# EE209_Schematic.net
KiCad netlist of a schematic drawn in Altium Designer
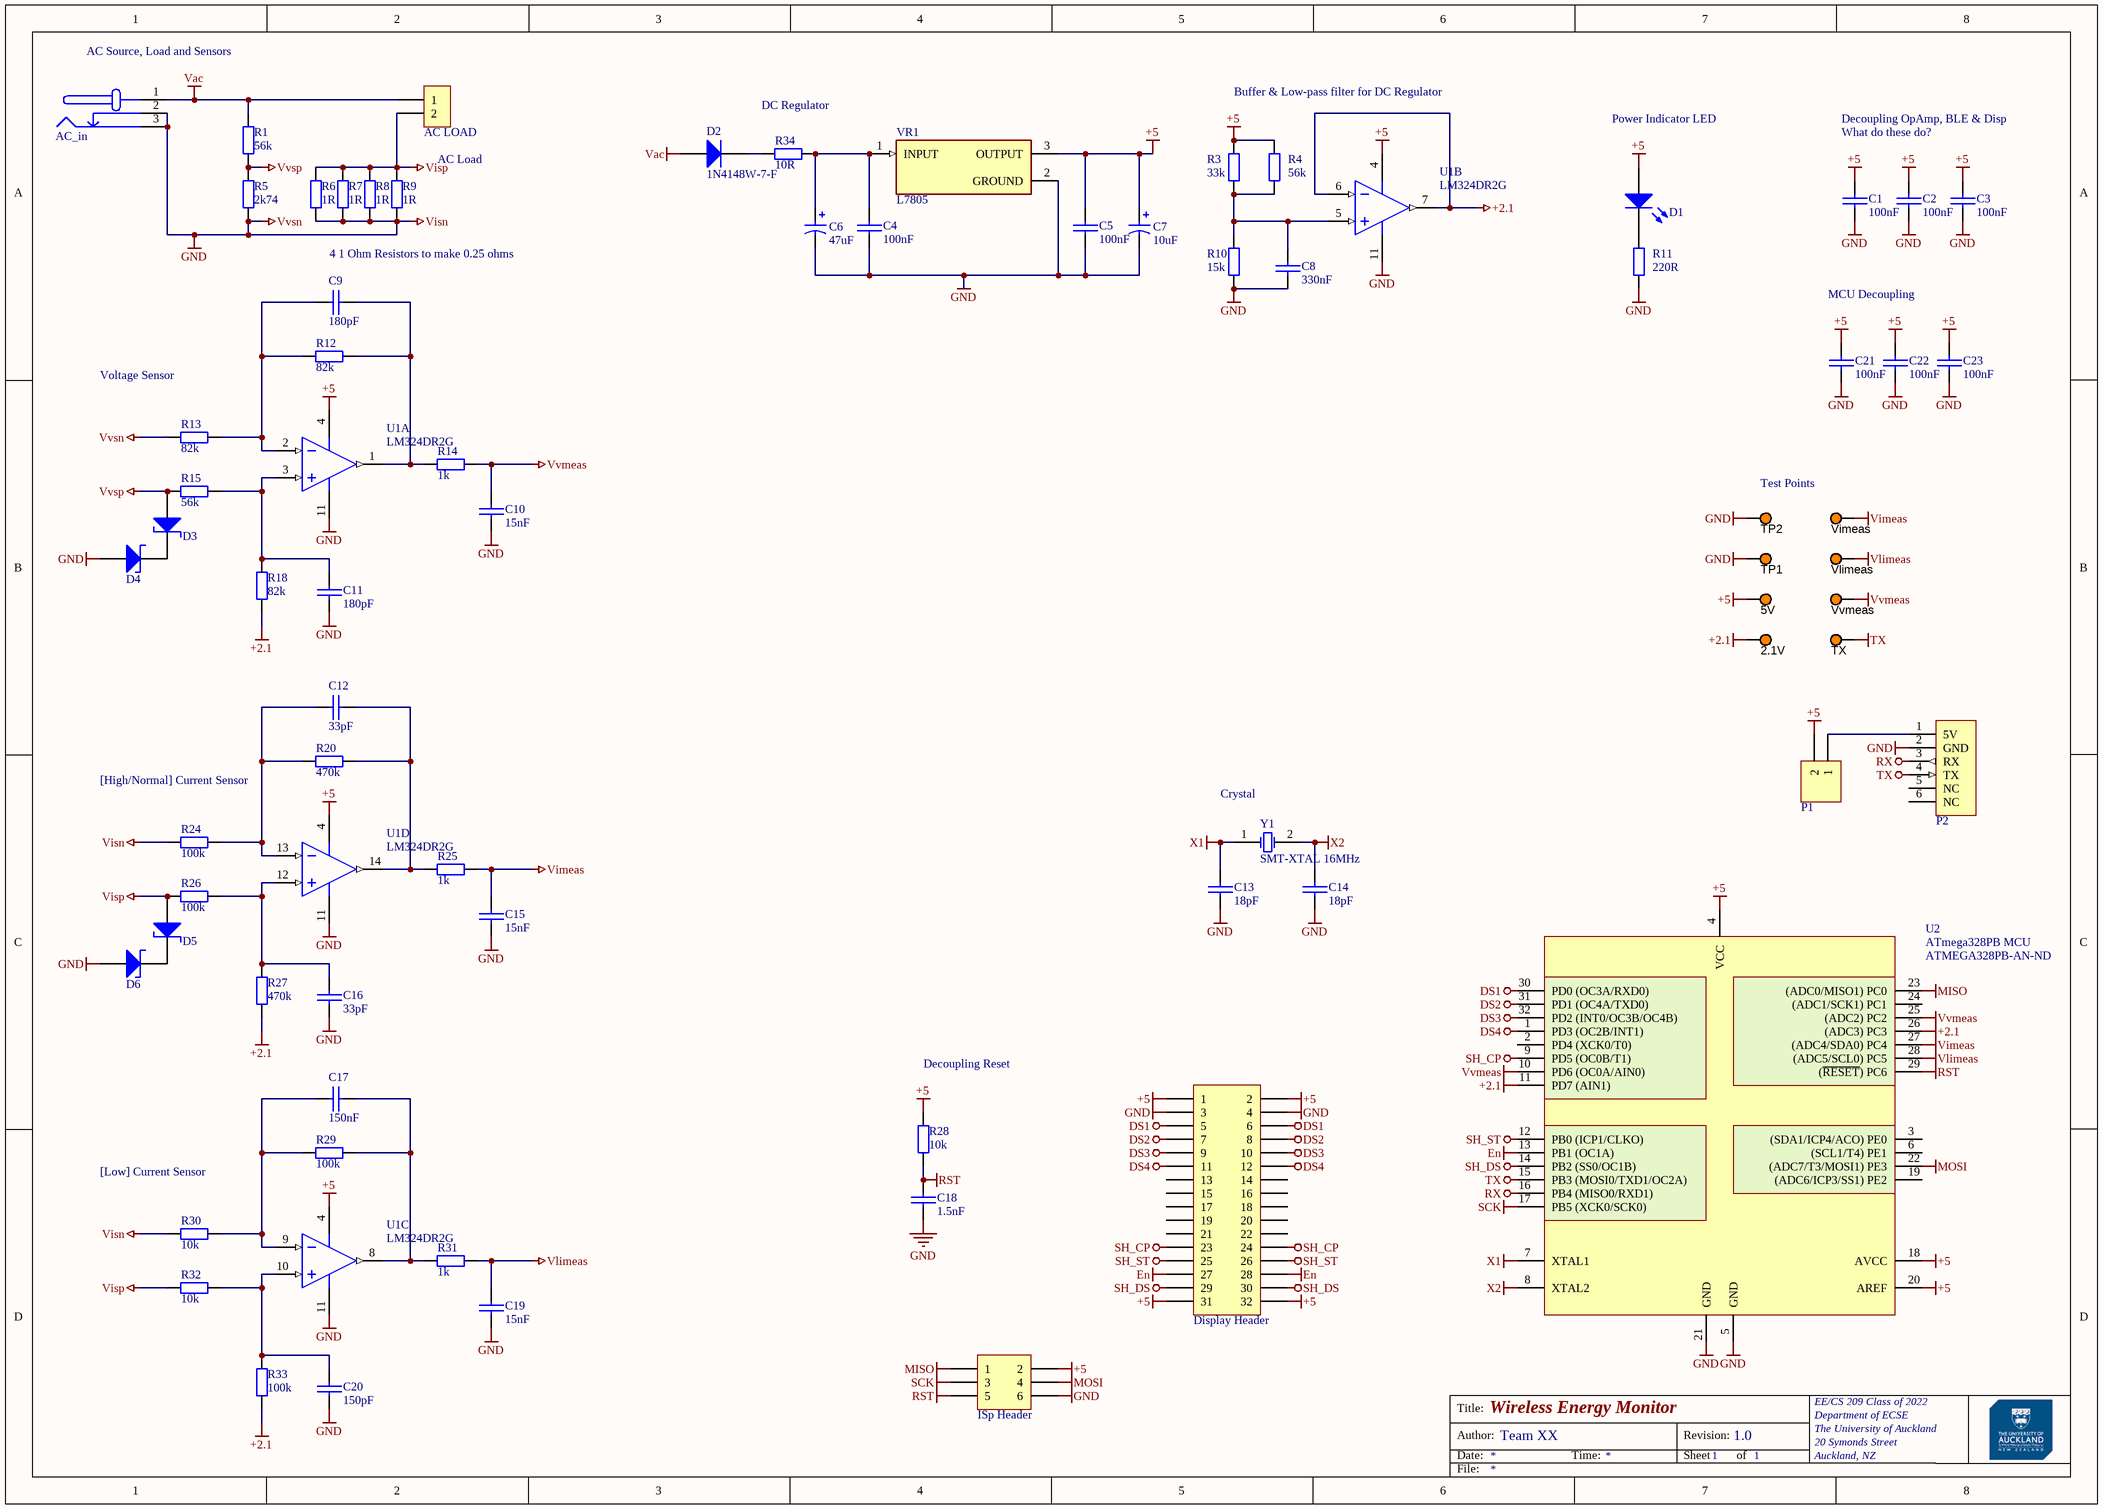
[diagram p0: EE209_Schematic.SchDoc]

(export (version "E")
  (design (tool "Eeschema 10.0.6"))
  (components
    (comp (ref "2.1V")
      (value "5003")
      (footprint "TP_TH")
      (description "Test Point, Orange, 1-Pin THD, RoHS")
      (libsource (lib "EE209_Library") (part "TestPoint"))
    )
    (comp (ref "5V")
      (value "5003")
      (footprint "TP_TH")
      (description "Test Point, Orange, 1-Pin THD, RoHS")
      (libsource (lib "EE209_Library") (part "TestPoint"))
    )
    (comp (ref "AC LOAD")
      (value "AC Load")
      (footprint "Dual Banana Plug")
      (description "Dual banana plugs connection to the AC load")
      (fields (field (name "PUBLISHER") "Altium Limited"))
      (libsource (lib "EE209_Library") (part "AC_Output"))
    )
    (comp (ref "AC_in")
      (value "DC barrel jack")
      (footprint "AC-Socket")
      (description "DC barrel jack connection to AC source")
      (libsource (lib "EE209_Library") (part "AC_Input"))
    )
    (comp (ref "C1")
      (value "100nF")
      (footprint "0805 CAP")
      (description "SMT ceramic capacitor 0805 size")
      (libsource (lib "EE209_Library") (part "CerCap_SMT_0805"))
    )
    (comp (ref "C2")
      (value "100nF")
      (footprint "0805 CAP")
      (description "SMT ceramic capacitor 0805 size")
      (libsource (lib "EE209_Library") (part "CerCap_SMT_0805"))
    )
    (comp (ref "C3")
      (value "100nF")
      (footprint "0805 CAP")
      (description "SMT ceramic capacitor 0805 size")
      (libsource (lib "EE209_Library") (part "CerCap_SMT_0805"))
    )
    (comp (ref "C4")
      (value "100nF")
      (footprint "0805 CAP")
      (description "SMT ceramic capacitor 0805 size")
      (libsource (lib "EE209_Library") (part "CerCap_SMT_0805"))
    )
    (comp (ref "C5")
      (value "100nF")
      (footprint "0805 CAP")
      (description "SMT ceramic capacitor 0805 size")
      (libsource (lib "EE209_Library") (part "CerCap_SMT_0805"))
    )
    (comp (ref "C6")
      (value "47uF")
      (footprint "CAP POL 8x5.4mm SMT")
      (description "CAP ALUM 22UF 20% 50V SMD (Model: UWX1H220MCL1GB)")
      (fields
        (field (name "MANUFACTURER") "Nichicon")
        (field (name "MANUFACTURER PART NUMBER") "UWX1V220MCL1GB")
      )
      (libsource (lib "EE209_Library") (part "ElecCap_SMT_8D0"))
    )
    (comp (ref "C7")
      (value "10uF")
      (footprint "CAP POL 8x5.4mm SMT")
      (description "CAP ALUM 22UF 20% 50V SMD (Model: UWX1H220MCL1GB)")
      (fields
        (field (name "MANUFACTURER") "Nichicon")
        (field (name "MANUFACTURER PART NUMBER") "UWX1V220MCL1GB")
      )
      (libsource (lib "EE209_Library") (part "ElecCap_SMT_8D0"))
    )
    (comp (ref "C8")
      (value "330nF")
      (footprint "0805 CAP")
      (description "SMT ceramic capacitor 0805 size")
      (libsource (lib "EE209_Library") (part "CerCap_SMT_0805"))
    )
    (comp (ref "C9")
      (value "180pF")
      (footprint "0805 CAP")
      (description "SMT ceramic capacitor 0805 size")
      (libsource (lib "EE209_Library") (part "CerCap_SMT_0805"))
    )
    (comp (ref "C10")
      (value "15nF")
      (footprint "0805 CAP")
      (description "SMT ceramic capacitor 0805 size")
      (libsource (lib "EE209_Library") (part "CerCap_SMT_0805"))
    )
    (comp (ref "C11")
      (value "180pF")
      (footprint "0805 CAP")
      (description "SMT ceramic capacitor 0805 size")
      (libsource (lib "EE209_Library") (part "CerCap_SMT_0805"))
    )
    (comp (ref "C12")
      (value "33pF")
      (footprint "0805 CAP")
      (description "SMT ceramic capacitor 0805 size")
      (libsource (lib "EE209_Library") (part "CerCap_SMT_0805"))
    )
    (comp (ref "C13")
      (value "18pF")
      (footprint "0805 CAP")
      (description "SMT ceramic capacitor 0805 size")
      (libsource (lib "EE209_Library") (part "CerCap_SMT_0805"))
    )
    (comp (ref "C14")
      (value "18pF")
      (footprint "0805 CAP")
      (description "SMT ceramic capacitor 0805 size")
      (libsource (lib "EE209_Library") (part "CerCap_SMT_0805"))
    )
    (comp (ref "C15")
      (value "15nF")
      (footprint "0805 CAP")
      (description "SMT ceramic capacitor 0805 size")
      (libsource (lib "EE209_Library") (part "CerCap_SMT_0805"))
    )
    (comp (ref "C16")
      (value "33pF")
      (footprint "0805 CAP")
      (description "SMT ceramic capacitor 0805 size")
      (libsource (lib "EE209_Library") (part "CerCap_SMT_0805"))
    )
    (comp (ref "C17")
      (value "150nF")
      (footprint "0805 CAP")
      (description "SMT ceramic capacitor 0805 size")
      (libsource (lib "EE209_Library") (part "CerCap_SMT_0805"))
    )
    (comp (ref "C18")
      (value "1.5nF")
      (footprint "0805 CAP")
      (description "SMT ceramic capacitor 0805 size")
      (libsource (lib "EE209_Library") (part "CerCap_SMT_0805"))
    )
    (comp (ref "C19")
      (value "15nF")
      (footprint "0805 CAP")
      (description "SMT ceramic capacitor 0805 size")
      (libsource (lib "EE209_Library") (part "CerCap_SMT_0805"))
    )
    (comp (ref "C20")
      (value "150pF")
      (footprint "0805 CAP")
      (description "SMT ceramic capacitor 0805 size")
      (libsource (lib "EE209_Library") (part "CerCap_SMT_0805"))
    )
    (comp (ref "C21")
      (value "100nF")
      (footprint "0805 CAP")
      (description "SMT ceramic capacitor 0805 size")
      (libsource (lib "EE209_Library") (part "CerCap_SMT_0805"))
    )
    (comp (ref "C22")
      (value "100nF")
      (footprint "0805 CAP")
      (description "SMT ceramic capacitor 0805 size")
      (libsource (lib "EE209_Library") (part "CerCap_SMT_0805"))
    )
    (comp (ref "C23")
      (value "100nF")
      (footprint "0805 CAP")
      (description "SMT ceramic capacitor 0805 size")
      (libsource (lib "EE209_Library") (part "CerCap_SMT_0805"))
    )
    (comp (ref "D1")
      (value "LTST-C170KGKT")
      (footprint "0805 LED")
      (description "SMT LED 0805 size")
      (fields (field (name "MANUFACTURER") "Lite-On Inc."))
      (libsource (lib "EE209_Library") (part "LED_SMT_0805"))
    )
    (comp (ref "D2")
      (value "1N4148W-7-F")
      (footprint "SOD123")
      (description "DIODE GEN PURP 100V 300MA SOD123")
      (fields
        (field (name "MANUFACTURER") "Diodes Incorporated")
        (field (name "MANUFACTURER PART NUMBER") "1N4148W-13-F")
      )
      (libsource (lib "EE209_Library") (part "1N4148_SMT_SOD123"))
    )
    (comp (ref "D3")
      (value "BZT52H-B4V7")
      (footprint "SOD123")
      (description "SMT zener diode with SOD123 package")
      (fields
        (field (name "MANUFACTURER") "Nexperia USA Inc.")
        (field (name "MANUFACTURER PART NUMBER") "BZT52H-B4V7,115")
      )
      (libsource (lib "EE209_Library") (part "Zener_SMT_SOD123"))
    )
    (comp (ref "D4")
      (value "BZT52H-B4V7")
      (footprint "SOD123")
      (description "SMT zener diode with SOD123 package")
      (fields
        (field (name "MANUFACTURER") "Nexperia USA Inc.")
        (field (name "MANUFACTURER PART NUMBER") "BZT52H-B4V7,115")
      )
      (libsource (lib "EE209_Library") (part "Zener_SMT_SOD123"))
    )
    (comp (ref "D5")
      (value "BZT52H-B4V7")
      (footprint "SOD123")
      (description "SMT zener diode with SOD123 package")
      (fields
        (field (name "MANUFACTURER") "Nexperia USA Inc.")
        (field (name "MANUFACTURER PART NUMBER") "BZT52H-B4V7,115")
      )
      (libsource (lib "EE209_Library") (part "Zener_SMT_SOD123"))
    )
    (comp (ref "D6")
      (value "BZT52H-B4V7")
      (footprint "SOD123")
      (description "SMT zener diode with SOD123 package")
      (fields
        (field (name "MANUFACTURER") "Nexperia USA Inc.")
        (field (name "MANUFACTURER PART NUMBER") "BZT52H-B4V7,115")
      )
      (libsource (lib "EE209_Library") (part "Zener_SMT_SOD123"))
    )
    (comp (ref "Display Header")
      (value "Display")
      (footprint "Display")
      (description "16-Pin Header Connecting Display")
      (libsource (lib "EE209_Library") (part "Display"))
    )
    (comp (ref "ISp Header")
      (value "Header 3X2")
      (footprint "ECE-BHDR2X3")
      (libsource (lib "ece components") (part "Header 3X2"))
    )
    (comp (ref "P1")
      (value "Header 2")
      (footprint "ece-HDR1X2")
      (description "Header, 2-Pin")
      (fields (field (name "PUBLISHER") "Altium Limited"))
      (libsource (lib "ece components") (part "Header 2"))
    )
    (comp (ref "P2")
      (value "BLE Module Header")
      (footprint "HM10_HDR1X6")
      (description "2.54mm pitch 6-pin header for BLE module")
      (fields (field (name "PUBLISHER") "Altium Limited"))
      (libsource (lib "EE209_Library") (part "BLEModule_TH"))
    )
    (comp (ref "R1")
      (value "56k")
      (footprint "0805 RES")
      (description "0805 resistor")
      (fields (field (name "PUBLISHER") "Altium Limited"))
      (libsource (lib "") (part "Res_SMT_0805_1"))
    )
    (comp (ref "R3")
      (value "33k")
      (footprint "0805 RES")
      (description "0805 resistor")
      (fields (field (name "PUBLISHER") "Altium Limited"))
      (libsource (lib "") (part "Res_SMT_0805_1"))
    )
    (comp (ref "R4")
      (value "56k")
      (footprint "0805 RES")
      (description "0805 resistor")
      (fields (field (name "PUBLISHER") "Altium Limited"))
      (libsource (lib "") (part "Res_SMT_0805_1"))
    )
    (comp (ref "R5")
      (value "2k74")
      (footprint "0805 RES")
      (description "0805 resistor")
      (fields (field (name "PUBLISHER") "Altium Limited"))
      (libsource (lib "") (part "Res_SMT_0805_1"))
    )
    (comp (ref "R6")
      (value "1R")
      (footprint "0805 RES")
      (description "0805 resistor")
      (fields (field (name "PUBLISHER") "Altium Limited"))
      (libsource (lib "") (part "Res_SMT_0805_1"))
    )
    (comp (ref "R7")
      (value "1R")
      (footprint "0805 RES")
      (description "0805 resistor")
      (fields (field (name "PUBLISHER") "Altium Limited"))
      (libsource (lib "") (part "Res_SMT_0805_1"))
    )
    (comp (ref "R8")
      (value "1R")
      (footprint "0805 RES")
      (description "0805 resistor")
      (fields (field (name "PUBLISHER") "Altium Limited"))
      (libsource (lib "") (part "Res_SMT_0805_1"))
    )
    (comp (ref "R9")
      (value "1R")
      (footprint "0805 RES")
      (description "0805 resistor")
      (fields (field (name "PUBLISHER") "Altium Limited"))
      (libsource (lib "") (part "Res_SMT_0805_1"))
    )
    (comp (ref "R10")
      (value "15k")
      (footprint "0805 RES")
      (description "0805 resistor")
      (fields (field (name "PUBLISHER") "Altium Limited"))
      (libsource (lib "") (part "Res_SMT_0805_1"))
    )
    (comp (ref "R11")
      (value "220R")
      (footprint "0805 RES")
      (description "0805 resistor")
      (fields (field (name "PUBLISHER") "Altium Limited"))
      (libsource (lib "") (part "Res_SMT_0805_1"))
    )
    (comp (ref "R12")
      (value "82k")
      (footprint "0805 RES")
      (description "0805 resistor")
      (fields (field (name "PUBLISHER") "Altium Limited"))
      (libsource (lib "EE209_Library") (part "Res_SMT_0805"))
    )
    (comp (ref "R13")
      (value "82k")
      (footprint "0805 RES")
      (description "0805 resistor")
      (fields (field (name "PUBLISHER") "Altium Limited"))
      (libsource (lib "") (part "Res_SMT_0805_3"))
    )
    (comp (ref "R14")
      (value "1k")
      (footprint "0805 RES")
      (description "0805 resistor")
      (fields (field (name "PUBLISHER") "Altium Limited"))
      (libsource (lib "EE209_Library") (part "Res_SMT_0805"))
    )
    (comp (ref "R15")
      (value "56k")
      (footprint "0805 RES")
      (description "0805 resistor")
      (fields (field (name "PUBLISHER") "Altium Limited"))
      (libsource (lib "") (part "Res_SMT_0805_3"))
    )
    (comp (ref "R18")
      (value "82k")
      (footprint "0805 RES")
      (description "0805 resistor")
      (fields (field (name "PUBLISHER") "Altium Limited"))
      (libsource (lib "") (part "Res_SMT_0805_2"))
    )
    (comp (ref "R20")
      (value "470k")
      (footprint "0805 RES")
      (description "0805 resistor")
      (fields (field (name "PUBLISHER") "Altium Limited"))
      (libsource (lib "EE209_Library") (part "Res_SMT_0805"))
    )
    (comp (ref "R24")
      (value "100k")
      (footprint "0805 RES")
      (description "0805 resistor")
      (fields (field (name "PUBLISHER") "Altium Limited"))
      (libsource (lib "") (part "Res_SMT_0805_3"))
    )
    (comp (ref "R25")
      (value "1k")
      (footprint "0805 RES")
      (description "0805 resistor")
      (fields (field (name "PUBLISHER") "Altium Limited"))
      (libsource (lib "EE209_Library") (part "Res_SMT_0805"))
    )
    (comp (ref "R26")
      (value "100k")
      (footprint "0805 RES")
      (description "0805 resistor")
      (fields (field (name "PUBLISHER") "Altium Limited"))
      (libsource (lib "") (part "Res_SMT_0805_3"))
    )
    (comp (ref "R27")
      (value "470k")
      (footprint "0805 RES")
      (description "0805 resistor")
      (fields (field (name "PUBLISHER") "Altium Limited"))
      (libsource (lib "") (part "Res_SMT_0805_2"))
    )
    (comp (ref "R28")
      (value "10k")
      (footprint "0805 RES")
      (description "0805 resistor")
      (fields (field (name "PUBLISHER") "Altium Limited"))
      (libsource (lib "") (part "Res_SMT_0805_1"))
    )
    (comp (ref "R29")
      (value "100k")
      (footprint "0805 RES")
      (description "0805 resistor")
      (fields (field (name "PUBLISHER") "Altium Limited"))
      (libsource (lib "EE209_Library") (part "Res_SMT_0805"))
    )
    (comp (ref "R30")
      (value "10k")
      (footprint "0805 RES")
      (description "0805 resistor")
      (fields (field (name "PUBLISHER") "Altium Limited"))
      (libsource (lib "") (part "Res_SMT_0805_3"))
    )
    (comp (ref "R31")
      (value "1k")
      (footprint "0805 RES")
      (description "0805 resistor")
      (fields (field (name "PUBLISHER") "Altium Limited"))
      (libsource (lib "EE209_Library") (part "Res_SMT_0805"))
    )
    (comp (ref "R32")
      (value "10k")
      (footprint "0805 RES")
      (description "0805 resistor")
      (fields (field (name "PUBLISHER") "Altium Limited"))
      (libsource (lib "") (part "Res_SMT_0805_3"))
    )
    (comp (ref "R33")
      (value "100k")
      (footprint "0805 RES")
      (description "0805 resistor")
      (fields (field (name "PUBLISHER") "Altium Limited"))
      (libsource (lib "") (part "Res_SMT_0805_2"))
    )
    (comp (ref "R34")
      (value "10R")
      (footprint "AXIAL-0.4")
      (description "Through hole resistor")
      (fields (field (name "PUBLISHER") "Altium Limited"))
      (libsource (lib "EE209_Library") (part "Res_TH_0AX4"))
    )
    (comp (ref "TP1")
      (value "5003")
      (footprint "TP_TH")
      (description "Test Point, Orange, 1-Pin THD, RoHS")
      (libsource (lib "EE209_Library") (part "TestPoint"))
    )
    (comp (ref "TP2")
      (value "5003")
      (footprint "TP_TH")
      (description "Test Point, Orange, 1-Pin THD, RoHS")
      (libsource (lib "EE209_Library") (part "TestPoint"))
    )
    (comp (ref "TX")
      (value "5003")
      (footprint "TP_TH")
      (description "Test Point, Orange, 1-Pin THD, RoHS")
      (libsource (lib "EE209_Library") (part "TestPoint"))
    )
    (comp (ref "U1")
      (value "LM324DR2G")
      (footprint "SOIC-14")
      (fields (field (name "MANUFACTURER") "On Semiconductor"))
      (libsource (lib "EE209_Library") (part "LM324DR_SMT_SOIC16"))
    )
    (comp (ref "U2")
      (value "ATmega328PB MCU")
      (footprint "32 - TQFP")
      (description "IC MCU 8BIT 32KB FLASH 32TQFP")
      (fields
        (field (name "MANUFACTURER") "Atmel")
        (field (name "MANUFACTURER PART NUMBER") "ATMEGA328PB-AN")
        (field (name "SUPPLIER PART NUMBER 1") "ATMEGA328PB-AN-ND")
      )
      (libsource (lib "EE209_Library") (part "ATmega328PB_SMT_TQFP32"))
    )
    (comp (ref "Vimeas")
      (value "5003")
      (footprint "TP_TH")
      (description "Test Point, Orange, 1-Pin THD, RoHS")
      (libsource (lib "EE209_Library") (part "TestPoint"))
    )
    (comp (ref "Vlimeas")
      (value "5003")
      (footprint "TP_TH")
      (description "Test Point, Orange, 1-Pin THD, RoHS")
      (libsource (lib "EE209_Library") (part "TestPoint"))
    )
    (comp (ref "VR1")
      (value "L7805")
      (footprint "TO255P1020X450X2000-3")
      (description "Standard Regulator Pos 5V 1.5A 3-Pin(3+Tab) TO-220FP Tube")
      (fields (field (name "MF") "STMicroelectronics"))
      (libsource (lib "L7805") (part "L7805"))
    )
    (comp (ref "Vvmeas")
      (value "5003")
      (footprint "TP_TH")
      (description "Test Point, Orange, 1-Pin THD, RoHS")
      (libsource (lib "EE209_Library") (part "TestPoint"))
    )
    (comp (ref "Y1")
      (value "SMT-XTAL 16MHz")
      (footprint "HC49-US")
      (description "9C-16.000MAAJ-T crystal 16.0000MHZ 18PF SMD")
      (fields
        (field (name "MANUFACTURER") "TXC CORPORATION")
        (field (name "MANUFACTURER PART NUMBER") "9C-16.000MAAJ-T")
      )
      (libsource (lib "EE209_Library") (part "TXC9C-16_XTAL_SMT"))
    )
  )
  (nets
    (net (code "1") (name "+2.1") (class "Default")
      (node (ref "2.1V") (pin "1") (pinfunction "1_1") (pintype "passive"))
      (node (ref "R18") (pin "2") (pinfunction "2_2") (pintype "passive"))
      (node (ref "R27") (pin "2") (pinfunction "2_2") (pintype "passive"))
      (node (ref "R33") (pin "2") (pinfunction "2_2") (pintype "passive"))
      (node (ref "U1") (pin "6") (pinfunction "IN2-_6") (pintype "input"))
      (node (ref "U1") (pin "7") (pinfunction "OUT2_7") (pintype "output"))
      (node (ref "U2") (pin "11") (pinfunction "PD7_(AIN1)_11") (pintype "passive"))
      (node (ref "U2") (pin "26") (pinfunction "(ADC3)_PC3_26") (pintype "passive"))
    )
    (net (code "2") (name "+5") (class "Default")
      (node (ref "5V") (pin "1") (pinfunction "1_1") (pintype "passive"))
      (node (ref "C1") (pin "1") (pinfunction "1_1") (pintype "passive"))
      (node (ref "C2") (pin "1") (pinfunction "1_1") (pintype "passive"))
      (node (ref "C21") (pin "1") (pinfunction "1_1") (pintype "passive"))
      (node (ref "C22") (pin "1") (pinfunction "1_1") (pintype "passive"))
      (node (ref "C23") (pin "1") (pinfunction "1_1") (pintype "passive"))
      (node (ref "C3") (pin "1") (pinfunction "1_1") (pintype "passive"))
      (node (ref "C5") (pin "1") (pinfunction "1_1") (pintype "passive"))
      (node (ref "C7") (pin "1") (pinfunction "1_1") (pintype "passive"))
      (node (ref "D1") (pin "1") (pinfunction "A_1") (pintype "passive"))
      (node (ref "Display Header") (pin "1") (pinfunction "1_1") (pintype "passive"))
      (node (ref "Display Header") (pin "2") (pinfunction "2_2") (pintype "passive"))
      (node (ref "Display Header") (pin "31") (pinfunction "31_31") (pintype "passive"))
      (node (ref "Display Header") (pin "32") (pinfunction "32_32") (pintype "passive"))
      (node (ref "ISp Header") (pin "2") (pinfunction "2_2") (pintype "passive"))
      (node (ref "P1") (pin "2") (pinfunction "2_2") (pintype "passive"))
      (node (ref "R28") (pin "2") (pinfunction "2_2") (pintype "passive"))
      (node (ref "R3") (pin "2") (pinfunction "2_2") (pintype "passive"))
      (node (ref "R4") (pin "2") (pinfunction "2_2") (pintype "passive"))
      (node (ref "U1") (pin "4") (pinfunction "VCC_4") (pintype "power_in"))
      (node (ref "U2") (pin "18") (pinfunction "AVCC_18") (pintype "passive"))
      (node (ref "U2") (pin "20") (pinfunction "AREF_20") (pintype "passive"))
      (node (ref "U2") (pin "4") (pinfunction "VCC_4") (pintype "passive"))
      (node (ref "VR1") (pin "3") (pinfunction "OUTPUT_3") (pintype "power_in"))
    )
    (net (code "3") (name "DS1") (class "Default")
      (node (ref "Display Header") (pin "5") (pinfunction "5_5") (pintype "passive"))
      (node (ref "Display Header") (pin "6") (pinfunction "6_6") (pintype "passive"))
      (node (ref "U2") (pin "30") (pinfunction "PD0_(OC3A/RXD0)_30") (pintype "passive"))
    )
    (net (code "4") (name "DS2") (class "Default")
      (node (ref "Display Header") (pin "7") (pinfunction "7_7") (pintype "passive"))
      (node (ref "Display Header") (pin "8") (pinfunction "8_8") (pintype "passive"))
      (node (ref "U2") (pin "31") (pinfunction "PD1_(OC4A/TXD0)_31") (pintype "passive"))
    )
    (net (code "5") (name "DS3") (class "Default")
      (node (ref "Display Header") (pin "10") (pinfunction "10_10") (pintype "passive"))
      (node (ref "Display Header") (pin "9") (pinfunction "9_9") (pintype "passive"))
      (node (ref "U2") (pin "32") (pinfunction "PD2_(INT0/OC3B/OC4B)_32") (pintype "passive"))
    )
    (net (code "6") (name "DS4") (class "Default")
      (node (ref "Display Header") (pin "11") (pinfunction "11_11") (pintype "passive"))
      (node (ref "Display Header") (pin "12") (pinfunction "12_12") (pintype "passive"))
      (node (ref "U2") (pin "1") (pinfunction "PD3_(OC2B/INT1)_1") (pintype "passive"))
    )
    (net (code "7") (name "En") (class "Default")
      (node (ref "Display Header") (pin "27") (pinfunction "27_27") (pintype "passive"))
      (node (ref "Display Header") (pin "28") (pinfunction "28_28") (pintype "passive"))
      (node (ref "U2") (pin "13") (pinfunction "PB1_(OC1A)_13") (pintype "passive"))
    )
    (net (code "8") (name "GND") (class "Default")
      (node (ref "AC_in") (pin "2") (pinfunction "GND_ALT_2") (pintype "power_in"))
      (node (ref "AC_in") (pin "3") (pinfunction "GND_3") (pintype "power_in"))
      (node (ref "C1") (pin "2") (pinfunction "2_2") (pintype "passive"))
      (node (ref "C10") (pin "1") (pinfunction "1_1") (pintype "passive"))
      (node (ref "C11") (pin "2") (pinfunction "2_2") (pintype "passive"))
      (node (ref "C13") (pin "2") (pinfunction "2_2") (pintype "passive"))
      (node (ref "C14") (pin "2") (pinfunction "2_2") (pintype "passive"))
      (node (ref "C15") (pin "1") (pinfunction "1_1") (pintype "passive"))
      (node (ref "C16") (pin "2") (pinfunction "2_2") (pintype "passive"))
      (node (ref "C18") (pin "2") (pinfunction "2_2") (pintype "passive"))
      (node (ref "C19") (pin "1") (pinfunction "1_1") (pintype "passive"))
      (node (ref "C2") (pin "2") (pinfunction "2_2") (pintype "passive"))
      (node (ref "C20") (pin "2") (pinfunction "2_2") (pintype "passive"))
      (node (ref "C21") (pin "2") (pinfunction "2_2") (pintype "passive"))
      (node (ref "C22") (pin "2") (pinfunction "2_2") (pintype "passive"))
      (node (ref "C23") (pin "2") (pinfunction "2_2") (pintype "passive"))
      (node (ref "C3") (pin "2") (pinfunction "2_2") (pintype "passive"))
      (node (ref "C4") (pin "2") (pinfunction "2_2") (pintype "passive"))
      (node (ref "C5") (pin "2") (pinfunction "2_2") (pintype "passive"))
      (node (ref "C6") (pin "2") (pinfunction "2_2") (pintype "passive"))
      (node (ref "C7") (pin "2") (pinfunction "2_2") (pintype "passive"))
      (node (ref "C8") (pin "2") (pinfunction "2_2") (pintype "passive"))
      (node (ref "D4") (pin "1") (pinfunction "A_1") (pintype "passive"))
      (node (ref "D6") (pin "1") (pinfunction "A_1") (pintype "passive"))
      (node (ref "Display Header") (pin "3") (pinfunction "3_3") (pintype "passive"))
      (node (ref "Display Header") (pin "4") (pinfunction "4_4") (pintype "passive"))
      (node (ref "ISp Header") (pin "6") (pinfunction "6_6") (pintype "passive"))
      (node (ref "P2") (pin "2") (pinfunction "GND_2") (pintype "passive"))
      (node (ref "R10") (pin "1") (pinfunction "1_1") (pintype "passive"))
      (node (ref "R11") (pin "1") (pinfunction "1_1") (pintype "passive"))
      (node (ref "R13") (pin "1") (pinfunction "1_1") (pintype "passive"))
      (node (ref "R24") (pin "1") (pinfunction "1_1") (pintype "passive"))
      (node (ref "R30") (pin "1") (pinfunction "1_1") (pintype "passive"))
      (node (ref "R5") (pin "1") (pinfunction "1_1") (pintype "passive"))
      (node (ref "R6") (pin "1") (pinfunction "1_1") (pintype "passive"))
      (node (ref "R7") (pin "1") (pinfunction "1_1") (pintype "passive"))
      (node (ref "R8") (pin "1") (pinfunction "1_1") (pintype "passive"))
      (node (ref "R9") (pin "1") (pinfunction "1_1") (pintype "passive"))
      (node (ref "TP1") (pin "1") (pinfunction "1_1") (pintype "passive"))
      (node (ref "TP2") (pin "1") (pinfunction "1_1") (pintype "passive"))
      (node (ref "U1") (pin "11") (pinfunction "VEE/GND_11") (pintype "power_in"))
      (node (ref "U2") (pin "21") (pinfunction "GND_21") (pintype "passive"))
      (node (ref "U2") (pin "5") (pinfunction "GND_5") (pintype "passive"))
      (node (ref "VR1") (pin "2") (pinfunction "GROUND_2") (pintype "power_in"))
    )
    (net (code "9") (name "MISO") (class "Default")
      (node (ref "ISp Header") (pin "1") (pinfunction "1_1") (pintype "passive"))
      (node (ref "U2") (pin "23") (pinfunction "(ADC0/MISO1)_PC0_23") (pintype "passive"))
    )
    (net (code "10") (name "MOSI") (class "Default")
      (node (ref "ISp Header") (pin "4") (pinfunction "4_4") (pintype "passive"))
      (node (ref "U2") (pin "22") (pinfunction "(ADC7/T3/MOSI1)_PE3_22") (pintype "passive"))
    )
    (net (code "11") (name "Net-(D1-K)") (class "Default")
      (node (ref "D1") (pin "2") (pinfunction "K_2") (pintype "passive"))
      (node (ref "R11") (pin "2") (pinfunction "2_2") (pintype "passive"))
    )
    (net (code "12") (name "Net-(D2-K)") (class "Default")
      (node (ref "D2") (pin "2") (pinfunction "K_2") (pintype "passive"))
      (node (ref "R34") (pin "1") (pinfunction "1_1") (pintype "passive"))
    )
    (net (code "13") (name "Net-(D3-K)") (class "Default")
      (node (ref "D3") (pin "2") (pinfunction "K_2") (pintype "passive"))
      (node (ref "D4") (pin "2") (pinfunction "K_2") (pintype "passive"))
    )
    (net (code "14") (name "Net-(D5-K)") (class "Default")
      (node (ref "D5") (pin "2") (pinfunction "K_2") (pintype "passive"))
      (node (ref "D6") (pin "2") (pinfunction "K_2") (pintype "passive"))
    )
    (net (code "15") (name "Net-(P2-5V)") (class "Default")
      (node (ref "P1") (pin "1") (pinfunction "1_1") (pintype "passive"))
      (node (ref "P2") (pin "1") (pinfunction "5V_1") (pintype "passive"))
    )
    (net (code "16") (name "Net-(U1A-IN1+)") (class "Default")
      (node (ref "C11") (pin "1") (pinfunction "1_1") (pintype "passive"))
      (node (ref "R15") (pin "2") (pinfunction "2_2") (pintype "passive"))
      (node (ref "R18") (pin "1") (pinfunction "1_1") (pintype "passive"))
      (node (ref "U1") (pin "3") (pinfunction "IN1+_3") (pintype "input"))
    )
    (net (code "17") (name "Net-(U1A-IN1-)") (class "Default")
      (node (ref "C9") (pin "1") (pinfunction "1_1") (pintype "passive"))
      (node (ref "R12") (pin "2") (pinfunction "2_2") (pintype "passive"))
      (node (ref "R13") (pin "2") (pinfunction "2_2") (pintype "passive"))
      (node (ref "U1") (pin "2") (pinfunction "IN1-_2") (pintype "input"))
    )
    (net (code "18") (name "Net-(U1A-OUT1)") (class "Default")
      (node (ref "C9") (pin "2") (pinfunction "2_2") (pintype "passive"))
      (node (ref "R12") (pin "1") (pinfunction "1_1") (pintype "passive"))
      (node (ref "R14") (pin "2") (pinfunction "2_2") (pintype "passive"))
      (node (ref "U1") (pin "1") (pinfunction "OUT1_1") (pintype "output"))
    )
    (net (code "19") (name "Net-(U1B-IN2+)") (class "Default")
      (node (ref "C8") (pin "1") (pinfunction "1_1") (pintype "passive"))
      (node (ref "R10") (pin "2") (pinfunction "2_2") (pintype "passive"))
      (node (ref "R3") (pin "1") (pinfunction "1_1") (pintype "passive"))
      (node (ref "R4") (pin "1") (pinfunction "1_1") (pintype "passive"))
      (node (ref "U1") (pin "5") (pinfunction "IN2+_5") (pintype "input"))
    )
    (net (code "20") (name "Net-(U1C-IN3+)") (class "Default")
      (node (ref "C20") (pin "1") (pinfunction "1_1") (pintype "passive"))
      (node (ref "R32") (pin "2") (pinfunction "2_2") (pintype "passive"))
      (node (ref "R33") (pin "1") (pinfunction "1_1") (pintype "passive"))
      (node (ref "U1") (pin "10") (pinfunction "IN3+_10") (pintype "input"))
    )
    (net (code "21") (name "Net-(U1C-IN3-)") (class "Default")
      (node (ref "C17") (pin "1") (pinfunction "1_1") (pintype "passive"))
      (node (ref "R29") (pin "2") (pinfunction "2_2") (pintype "passive"))
      (node (ref "R30") (pin "2") (pinfunction "2_2") (pintype "passive"))
      (node (ref "U1") (pin "9") (pinfunction "IN3-_9") (pintype "input"))
    )
    (net (code "22") (name "Net-(U1C-OUT3)") (class "Default")
      (node (ref "C17") (pin "2") (pinfunction "2_2") (pintype "passive"))
      (node (ref "R29") (pin "1") (pinfunction "1_1") (pintype "passive"))
      (node (ref "R31") (pin "2") (pinfunction "2_2") (pintype "passive"))
      (node (ref "U1") (pin "8") (pinfunction "OUT3_8") (pintype "output"))
    )
    (net (code "23") (name "Net-(U1D-IN4+)") (class "Default")
      (node (ref "C16") (pin "1") (pinfunction "1_1") (pintype "passive"))
      (node (ref "R26") (pin "2") (pinfunction "2_2") (pintype "passive"))
      (node (ref "R27") (pin "1") (pinfunction "1_1") (pintype "passive"))
      (node (ref "U1") (pin "12") (pinfunction "IN4+_12") (pintype "input"))
    )
    (net (code "24") (name "Net-(U1D-IN4-)") (class "Default")
      (node (ref "C12") (pin "1") (pinfunction "1_1") (pintype "passive"))
      (node (ref "R20") (pin "2") (pinfunction "2_2") (pintype "passive"))
      (node (ref "R24") (pin "2") (pinfunction "2_2") (pintype "passive"))
      (node (ref "U1") (pin "13") (pinfunction "IN4-_13") (pintype "input"))
    )
    (net (code "25") (name "Net-(U1D-OUT4)") (class "Default")
      (node (ref "C12") (pin "2") (pinfunction "2_2") (pintype "passive"))
      (node (ref "R20") (pin "1") (pinfunction "1_1") (pintype "passive"))
      (node (ref "R25") (pin "2") (pinfunction "2_2") (pintype "passive"))
      (node (ref "U1") (pin "14") (pinfunction "OUT4_14") (pintype "output"))
    )
    (net (code "26") (name "Net-(VR1-INPUT)") (class "Default")
      (node (ref "C4") (pin "1") (pinfunction "1_1") (pintype "passive"))
      (node (ref "C6") (pin "1") (pinfunction "1_1") (pintype "passive"))
      (node (ref "R34") (pin "2") (pinfunction "2_2") (pintype "passive"))
      (node (ref "VR1") (pin "1") (pinfunction "INPUT_1") (pintype "input"))
    )
    (net (code "27") (name "RST") (class "Default")
      (node (ref "C18") (pin "1") (pinfunction "1_1") (pintype "passive"))
      (node (ref "ISp Header") (pin "5") (pinfunction "5_5") (pintype "passive"))
      (node (ref "R28") (pin "1") (pinfunction "1_1") (pintype "passive"))
      (node (ref "U2") (pin "29") (pinfunction "(~{RESET})_PC6_29") (pintype "passive"))
    )
    (net (code "28") (name "RX") (class "Default")
      (node (ref "P2") (pin "3") (pinfunction "RX_3") (pintype "output"))
      (node (ref "U2") (pin "16") (pinfunction "PB4_(MISO0/RXD1)_16") (pintype "passive"))
    )
    (net (code "29") (name "SCK") (class "Default")
      (node (ref "ISp Header") (pin "3") (pinfunction "3_3") (pintype "passive"))
      (node (ref "U2") (pin "17") (pinfunction "PB5_(XCK0/SCK0)_17") (pintype "passive"))
    )
    (net (code "30") (name "SH_CP") (class "Default")
      (node (ref "Display Header") (pin "23") (pinfunction "23_23") (pintype "passive"))
      (node (ref "Display Header") (pin "24") (pinfunction "24_24") (pintype "passive"))
      (node (ref "U2") (pin "9") (pinfunction "PD5_(OC0B/T1)_9") (pintype "passive"))
    )
    (net (code "31") (name "SH_DS") (class "Default")
      (node (ref "Display Header") (pin "29") (pinfunction "29_29") (pintype "passive"))
      (node (ref "Display Header") (pin "30") (pinfunction "30_30") (pintype "passive"))
      (node (ref "U2") (pin "14") (pinfunction "PB2_(SS0/OC1B)_14") (pintype "passive"))
    )
    (net (code "32") (name "SH_ST") (class "Default")
      (node (ref "Display Header") (pin "25") (pinfunction "25_25") (pintype "passive"))
      (node (ref "Display Header") (pin "26") (pinfunction "26_26") (pintype "passive"))
      (node (ref "U2") (pin "12") (pinfunction "PB0_(ICP1/CLKO)_12") (pintype "passive"))
    )
    (net (code "33") (name "TX") (class "Default")
      (node (ref "P2") (pin "4") (pinfunction "TX_4") (pintype "input"))
      (node (ref "TX") (pin "1") (pinfunction "1_1") (pintype "passive"))
      (node (ref "U2") (pin "15") (pinfunction "PB3_(MOSI0/TXD1/OC2A)_15") (pintype "passive"))
    )
    (net (code "34") (name "Vac") (class "Default")
      (node (ref "AC LOAD") (pin "1") (pinfunction "1_1") (pintype "passive"))
      (node (ref "AC_in") (pin "1") (pinfunction "VCC_1") (pintype "power_in"))
      (node (ref "D2") (pin "1") (pinfunction "A_1") (pintype "passive"))
      (node (ref "R1") (pin "2") (pinfunction "2_2") (pintype "passive"))
    )
    (net (code "35") (name "Vimeas") (class "Default")
      (node (ref "C15") (pin "2") (pinfunction "2_2") (pintype "passive"))
      (node (ref "R25") (pin "1") (pinfunction "1_1") (pintype "passive"))
      (node (ref "U2") (pin "27") (pinfunction "(ADC4/SDA0)_PC4_27") (pintype "passive"))
      (node (ref "Vimeas") (pin "1") (pinfunction "1_1") (pintype "passive"))
    )
    (net (code "36") (name "Visp") (class "Default")
      (node (ref "AC LOAD") (pin "2") (pinfunction "2_2") (pintype "passive"))
      (node (ref "D5") (pin "1") (pinfunction "A_1") (pintype "passive"))
      (node (ref "R26") (pin "1") (pinfunction "1_1") (pintype "passive"))
      (node (ref "R32") (pin "1") (pinfunction "1_1") (pintype "passive"))
      (node (ref "R6") (pin "2") (pinfunction "2_2") (pintype "passive"))
      (node (ref "R7") (pin "2") (pinfunction "2_2") (pintype "passive"))
      (node (ref "R8") (pin "2") (pinfunction "2_2") (pintype "passive"))
      (node (ref "R9") (pin "2") (pinfunction "2_2") (pintype "passive"))
    )
    (net (code "37") (name "Vlimeas") (class "Default")
      (node (ref "C19") (pin "2") (pinfunction "2_2") (pintype "passive"))
      (node (ref "R31") (pin "1") (pinfunction "1_1") (pintype "passive"))
      (node (ref "U2") (pin "28") (pinfunction "(ADC5/SCL0)_PC5_28") (pintype "passive"))
      (node (ref "Vlimeas") (pin "1") (pinfunction "1_1") (pintype "passive"))
    )
    (net (code "38") (name "Vvmeas") (class "Default")
      (node (ref "C10") (pin "2") (pinfunction "2_2") (pintype "passive"))
      (node (ref "R14") (pin "1") (pinfunction "1_1") (pintype "passive"))
      (node (ref "U2") (pin "10") (pinfunction "PD6_(OC0A/AIN0)_10") (pintype "passive"))
      (node (ref "U2") (pin "25") (pinfunction "(ADC2)_PC2_25") (pintype "passive"))
      (node (ref "Vvmeas") (pin "1") (pinfunction "1_1") (pintype "passive"))
    )
    (net (code "39") (name "Vvsp") (class "Default")
      (node (ref "D3") (pin "1") (pinfunction "A_1") (pintype "passive"))
      (node (ref "R1") (pin "1") (pinfunction "1_1") (pintype "passive"))
      (node (ref "R15") (pin "1") (pinfunction "1_1") (pintype "passive"))
      (node (ref "R5") (pin "2") (pinfunction "2_2") (pintype "passive"))
    )
    (net (code "40") (name "X1") (class "Default")
      (node (ref "C13") (pin "1") (pinfunction "1_1") (pintype "passive"))
      (node (ref "U2") (pin "7") (pinfunction "XTAL1_7") (pintype "passive"))
      (node (ref "Y1") (pin "1") (pinfunction "OSC1_1") (pintype "passive"))
    )
    (net (code "41") (name "X2") (class "Default")
      (node (ref "C14") (pin "1") (pinfunction "1_1") (pintype "passive"))
      (node (ref "U2") (pin "8") (pinfunction "XTAL2_8") (pintype "passive"))
      (node (ref "Y1") (pin "2") (pinfunction "OSC2_2") (pintype "passive"))
    )
    (net (code "42") (name "unconnected-(Display Header-Pad13)") (class "Default")
      (node (ref "Display Header") (pin "13") (pinfunction "13_13") (pintype "passive"))
    )
    (net (code "43") (name "unconnected-(Display Header-Pad14)") (class "Default")
      (node (ref "Display Header") (pin "14") (pinfunction "14_14") (pintype "passive"))
    )
    (net (code "44") (name "unconnected-(Display Header-Pad15)") (class "Default")
      (node (ref "Display Header") (pin "15") (pinfunction "15_15") (pintype "passive"))
    )
    (net (code "45") (name "unconnected-(Display Header-Pad16)") (class "Default")
      (node (ref "Display Header") (pin "16") (pinfunction "16_16") (pintype "passive"))
    )
    (net (code "46") (name "unconnected-(Display Header-Pad17)") (class "Default")
      (node (ref "Display Header") (pin "17") (pinfunction "17_17") (pintype "passive"))
    )
    (net (code "47") (name "unconnected-(Display Header-Pad18)") (class "Default")
      (node (ref "Display Header") (pin "18") (pinfunction "18_18") (pintype "passive"))
    )
    (net (code "48") (name "unconnected-(Display Header-Pad19)") (class "Default")
      (node (ref "Display Header") (pin "19") (pinfunction "19_19") (pintype "passive"))
    )
    (net (code "49") (name "unconnected-(Display Header-Pad20)") (class "Default")
      (node (ref "Display Header") (pin "20") (pinfunction "20_20") (pintype "passive"))
    )
    (net (code "50") (name "unconnected-(Display Header-Pad21)") (class "Default")
      (node (ref "Display Header") (pin "21") (pinfunction "21_21") (pintype "passive"))
    )
    (net (code "51") (name "unconnected-(Display Header-Pad22)") (class "Default")
      (node (ref "Display Header") (pin "22") (pinfunction "22_22") (pintype "passive"))
    )
    (net (code "52") (name "unconnected-(P2-NC-Pad5)") (class "Default")
      (node (ref "P2") (pin "5") (pinfunction "NC_5") (pintype "passive"))
    )
    (net (code "53") (name "unconnected-(P2-NC-Pad6)") (class "Default")
      (node (ref "P2") (pin "6") (pinfunction "NC_6") (pintype "passive"))
    )
    (net (code "54") (name "unconnected-(U2-(ADC1{slash}SCK1)_PC1-Pad24)") (class "Default")
      (node (ref "U2") (pin "24") (pinfunction "(ADC1/SCK1)_PC1_24") (pintype "passive"))
    )
    (net (code "55") (name "unconnected-(U2-(ADC6{slash}ICP3{slash}SS1)_PE2-Pad19)") (class "Default")
      (node (ref "U2") (pin "19") (pinfunction "(ADC6/ICP3/SS1)_PE2_19") (pintype "passive"))
    )
    (net (code "56") (name "unconnected-(U2-(SCL1{slash}T4)_PE1-Pad6)") (class "Default")
      (node (ref "U2") (pin "6") (pinfunction "(SCL1/T4)_PE1_6") (pintype "passive"))
    )
    (net (code "57") (name "unconnected-(U2-(SDA1{slash}ICP4{slash}ACO)_PE0-Pad3)") (class "Default")
      (node (ref "U2") (pin "3") (pinfunction "(SDA1/ICP4/ACO)_PE0_3") (pintype "passive"))
    )
    (net (code "58") (name "unconnected-(U2-PD4_(XCK0{slash}T0)-Pad2)") (class "Default")
      (node (ref "U2") (pin "2") (pinfunction "PD4_(XCK0/T0)_2") (pintype "passive"))
    )
  )
)
